# LM386-Audio-Amplifier.net
KiCad netlist of a schematic drawn in EAGLE
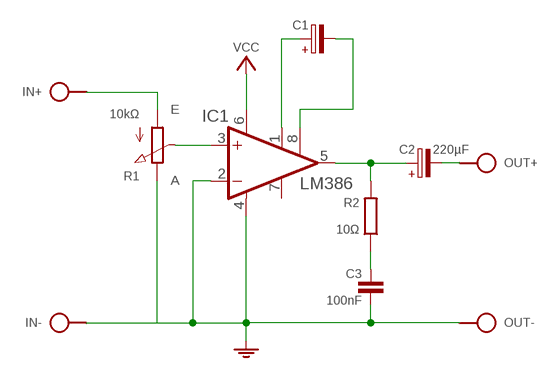
[diagram p0: schematic, sheet 1]

(export (version "E")
  (design (tool "Eeschema 10.0.6"))
  (components
    (comp (ref "C1")
      (value "CPOL-HE2,5-3")
      (footprint "eagle-import:E2,5-3")
      (libsource (lib "eagle-import") (part "CPOL-HE2,5-3"))
    )
    (comp (ref "C2")
      (value "220µF")
      (footprint "eagle-import:E5-5")
      (libsource (lib "eagle-import") (part "CPOL-HE5-5"))
    )
    (comp (ref "C3")
      (value "100nF")
      (footprint "eagle-import:C050-020X044")
      (libsource (lib "eagle-import") (part "C050-020X044"))
    )
    (comp (ref "IC1")
      (value "LM386")
      (footprint "eagle-import:DIL08")
      (libsource (lib "eagle-import") (part "LM386?-N1"))
    )
    (comp (ref "IN")
      (value "SPAD+-+-")
      (footprint "eagle-import:SPAD+-")
      (libsource (lib "eagle-import") (part "SPAD+-+-"))
    )
    (comp (ref "OUT")
      (value "SPAD+--+")
      (footprint "eagle-import:SPAD-+")
      (libsource (lib "eagle-import") (part "SPAD+--+"))
    )
    (comp (ref "R1")
      (value "10kΩ")
      (footprint "eagle-import:CONN-3P")
      (libsource (lib "eagle-import") (part "POT-3P"))
    )
    (comp (ref "R2")
      (value "10Ω")
      (footprint "eagle-import:0204_10-V")
      (libsource (lib "eagle-import") (part "R0204/10-V"))
    )
    (comp (ref "S1")
      (value "4-12V")
      (footprint "eagle-import:PWR-R")
      (libsource (lib "eagle-import") (part "VCC_GNDPWR-R"))
    )
  )
  (nets
    (net (code "1") (name "Net-(C1-Pad+)") (class "Default")
      (node (ref "C1") (pin "+") (pinfunction "+_+") (pintype "passive"))
      (node (ref "IC1") (pin "1") (pinfunction "GAIN_1") (pintype "passive"))
    )
    (net (code "2") (name "Net-(C1-Pad-)") (class "Default")
      (node (ref "C1") (pin "-") (pinfunction "-_-") (pintype "passive"))
      (node (ref "IC1") (pin "8") (pinfunction "GAIN_8") (pintype "passive"))
    )
    (net (code "3") (name "Net-(IC1-+IN)") (class "Default")
      (node (ref "IC1") (pin "3") (pinfunction "+IN_3") (pintype "input"))
      (node (ref "R1") (pin "2") (pinfunction "S_2") (pintype "passive"))
    )
    (net (code "4") (name "Net-(IC1--IN)") (class "Default")
      (node (ref "C3") (pin "2") (pinfunction "2_2") (pintype "passive"))
      (node (ref "IC1") (pin "2") (pinfunction "-IN_2") (pintype "input"))
      (node (ref "IC1") (pin "4") (pinfunction "GND_4") (pintype "power_in"))
      (node (ref "IN") (pin "1") (pinfunction "P$1_1") (pintype "passive"))
      (node (ref "OUT") (pin "1") (pinfunction "P$1_1") (pintype "passive"))
      (node (ref "R1") (pin "3") (pinfunction "E_3") (pintype "passive"))
      (node (ref "S1") (pin "1") (pinfunction "GND_1") (pintype "power_in"))
    )
    (net (code "5") (name "Net-(IC1-OUT)") (class "Default")
      (node (ref "C2") (pin "+") (pinfunction "+_+") (pintype "passive"))
      (node (ref "IC1") (pin "5") (pinfunction "OUT_5") (pintype "output"))
      (node (ref "R2") (pin "1") (pinfunction "2_1") (pintype "passive"))
    )
    (net (code "6") (name "Net-(IC1-VS)") (class "Default")
      (node (ref "IC1") (pin "6") (pinfunction "VS_6") (pintype "power_in"))
      (node (ref "S1") (pin "2") (pinfunction "VCC_2") (pintype "power_in"))
    )
    (net (code "7") (name "Net-(INA-P$1)") (class "Default")
      (node (ref "IN") (pin "2") (pinfunction "P$1_2") (pintype "passive"))
      (node (ref "R1") (pin "1") (pinfunction "A_1") (pintype "passive"))
    )
    (net (code "8") (name "Net-(OUTA-P$1)") (class "Default")
      (node (ref "C2") (pin "-") (pinfunction "-_-") (pintype "passive"))
      (node (ref "OUT") (pin "2") (pinfunction "P$1_2") (pintype "passive"))
    )
    (net (code "9") (name "Net-(R2-1)") (class "Default")
      (node (ref "C3") (pin "1") (pinfunction "1_1") (pintype "passive"))
      (node (ref "R2") (pin "2") (pinfunction "1_2") (pintype "passive"))
    )
    (net (code "10") (name "unconnected-(IC1-BYPASS-Pad7)") (class "Default")
      (node (ref "IC1") (pin "7") (pinfunction "BYPASS_7") (pintype "passive"))
    )
  )
)
